# AMC_Box_Mainboard.net
KiCad netlist of a schematic drawn in Altium Designer
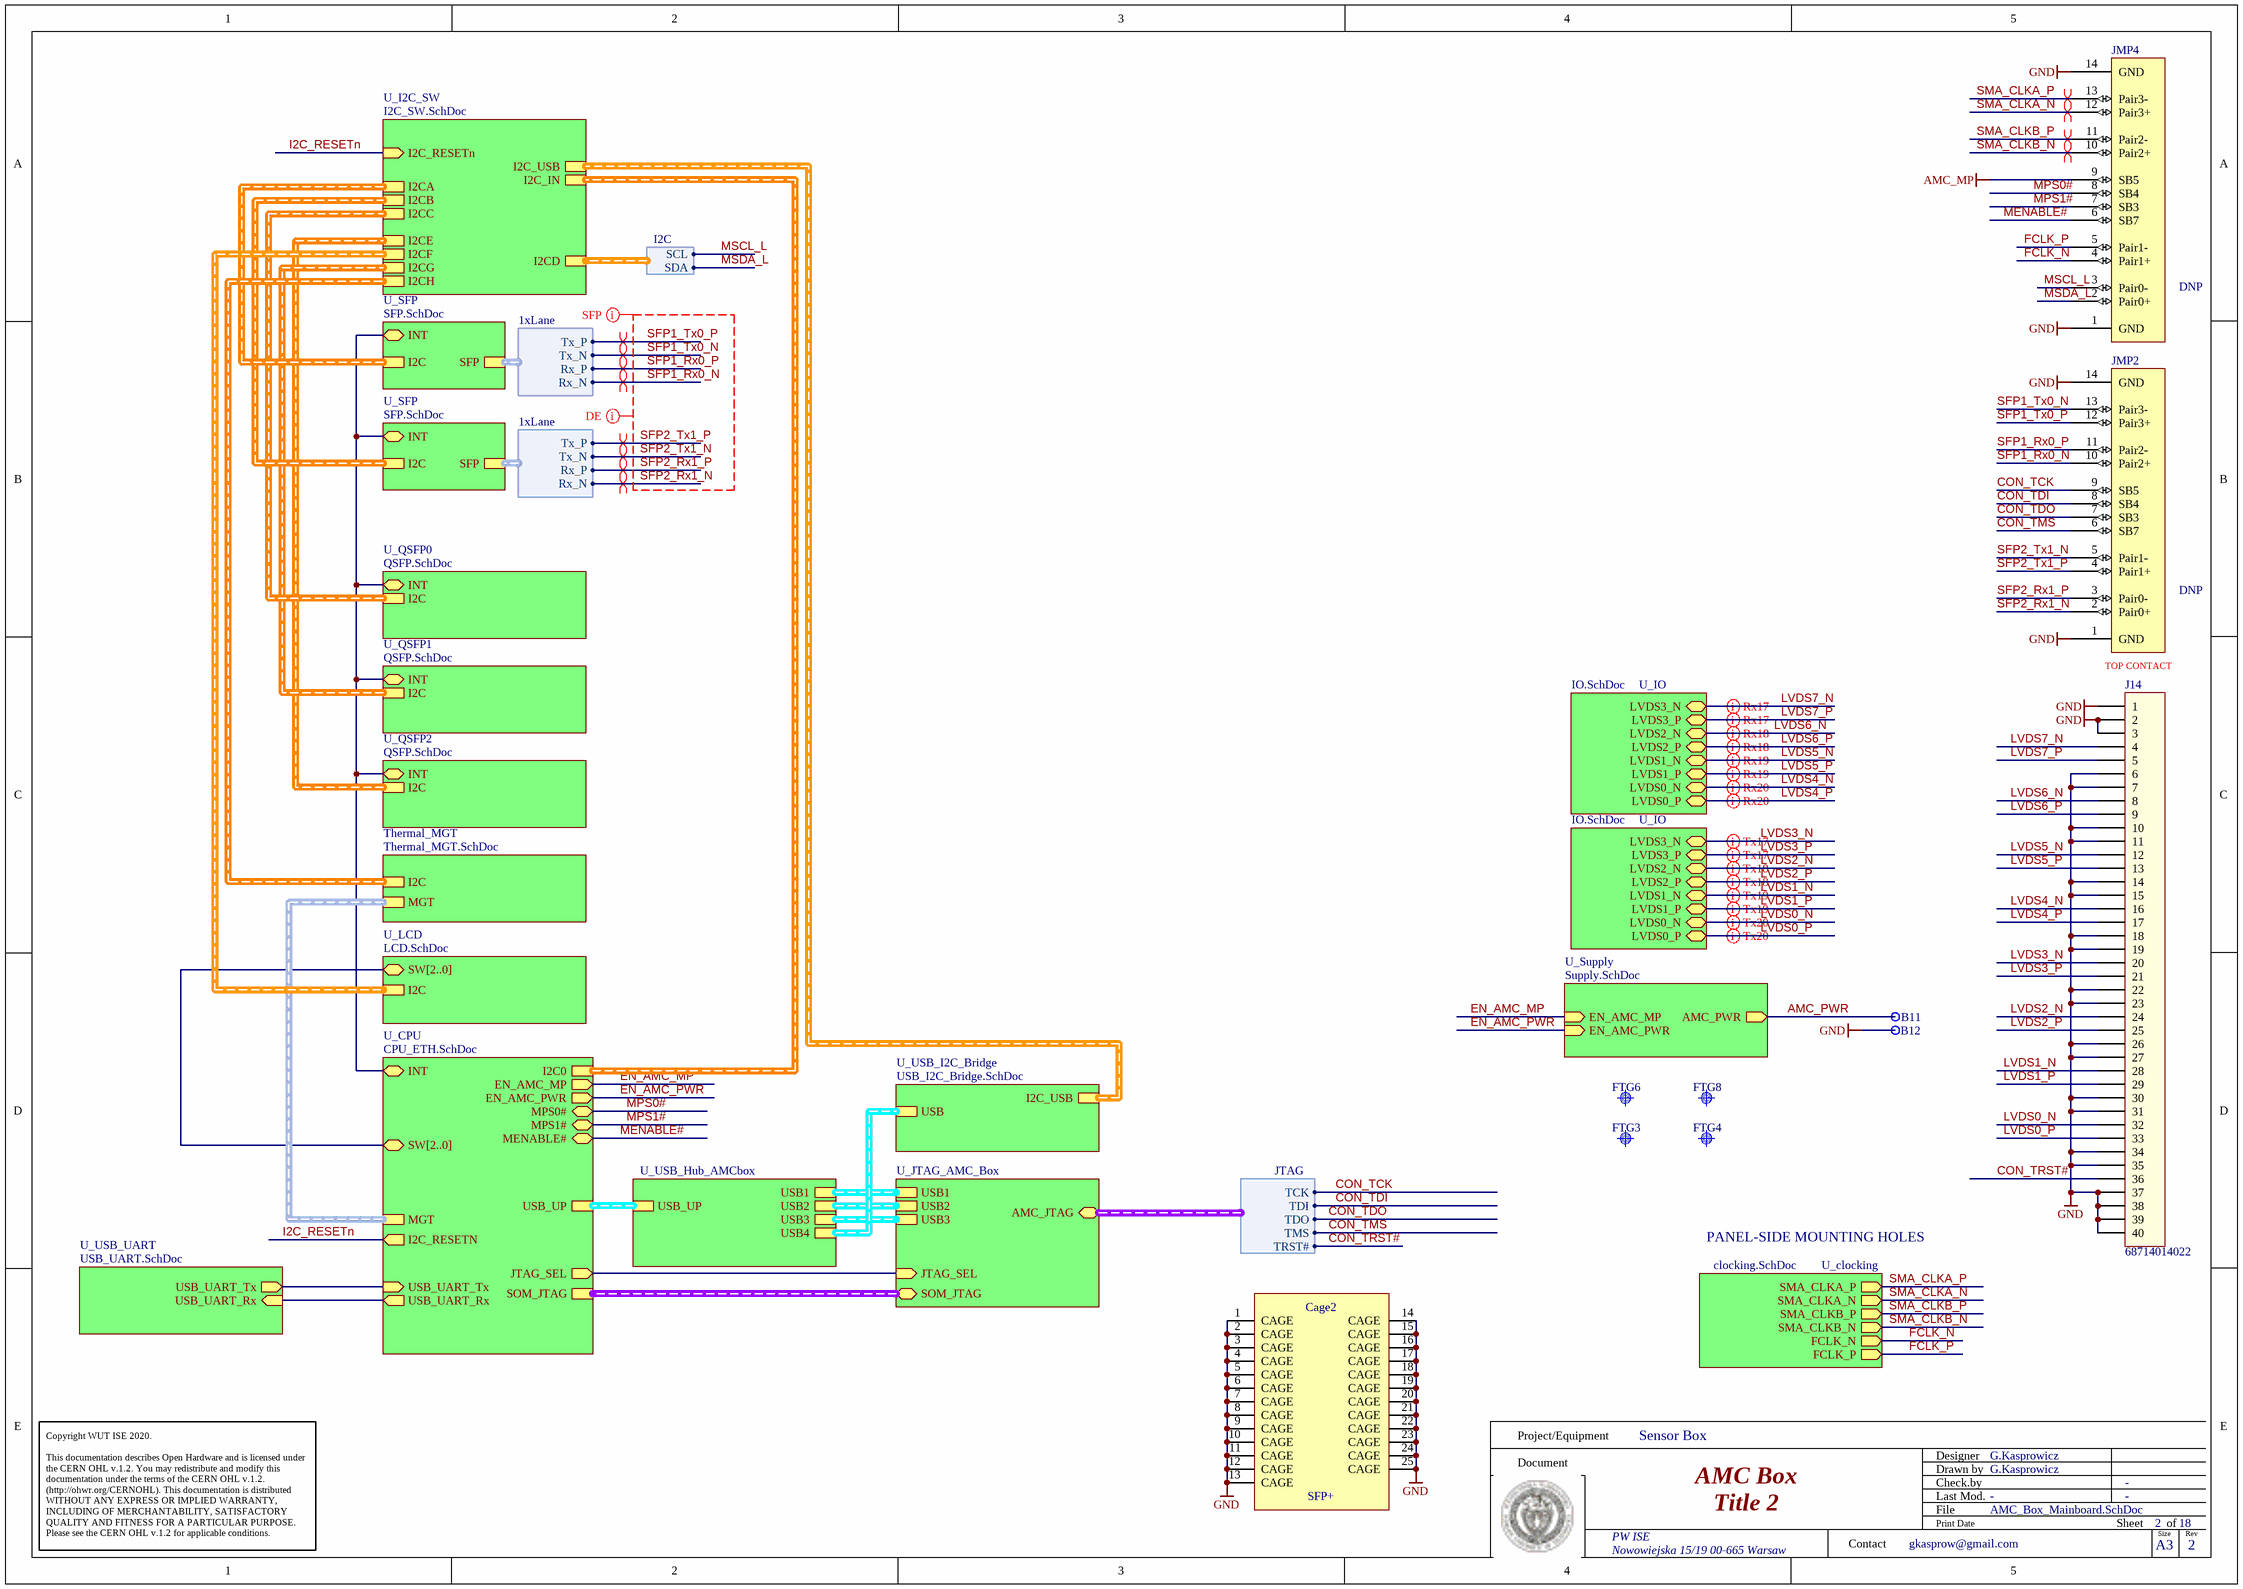
[diagram p0: AMC_Box_Mainboard.SchDoc]

(export (version "E")
  (design (tool "Eeschema 10.0.6"))
  (components
    (comp (ref "B11")
      (value "Plated Hole")
      (footprint "c200h150")
      (description "Single Terminal Socket")
      (fields (field (name "PART NUMBER") "PLATED_HOLE1.5_PAD2.0") (field (name "AUTHOR") "CERN DEM JLC"))
      (libsource (lib "Eletro-mechanical") (part "Single Terminal Socket"))
    )
    (comp (ref "B12")
      (value "Plated Hole")
      (footprint "c200h150")
      (description "Single Terminal Socket")
      (fields (field (name "PART NUMBER") "PLATED_HOLE1.5_PAD2.0") (field (name "AUTHOR") "CERN DEM JLC"))
      (libsource (lib "Eletro-mechanical") (part "Single Terminal Socket"))
    )
    (comp (ref "Cage2")
      (value "SFP+")
      (footprint "TYCO_2007263-1")
      (description "SFP 1x2 Cage (25Pins)")
      (fields
        (field (name "PART NUMBER") "TYCO_2007263-1")
        (field (name "MANUFACTURER") "TYCO ELECTRONICS")
        (field (name "AUTHOR") "CERN DEM JLC")
      )
      (libsource (lib "Connectors") (part "SFP 1x2 Cage (25Pins)"))
    )
    (comp (ref "FTG3")
      (value "Use only in PCB")
      (footprint "FIDUCIAL_TOP_S100-200")
      (description "Fiducial Target")
      (fields (field (name "PART NUMBER") "FIDUCIAL_TARGET_S100-200") (field (name "AUTHOR") "CERN DEM JLC"))
      (libsource (lib "Eletro-mechanical") (part "Fiducial Target"))
    )
    (comp (ref "FTG4")
      (value "Use only in PCB")
      (footprint "FIDUCIAL_TOP_C100-200")
      (description "Fiducial Target")
      (fields (field (name "PART NUMBER") "FIDUCIAL_TARGET_C100-200") (field (name "AUTHOR") "CERN DEM JLC"))
      (libsource (lib "Eletro-mechanical") (part "Fiducial Target"))
    )
    (comp (ref "FTG6")
      (value "Use only in PCB")
      (footprint "FIDUCIAL_TOP_S100-200")
      (description "Fiducial Target")
      (fields (field (name "PART NUMBER") "FIDUCIAL_TARGET_S100-200") (field (name "AUTHOR") "CERN DEM JLC"))
      (libsource (lib "Eletro-mechanical") (part "Fiducial Target"))
    )
    (comp (ref "FTG8")
      (value "Use only in PCB")
      (footprint "FIDUCIAL_TOP_C100-200")
      (description "Fiducial Target")
      (fields (field (name "PART NUMBER") "FIDUCIAL_TARGET_C100-200") (field (name "AUTHOR") "CERN DEM JLC"))
      (libsource (lib "Eletro-mechanical") (part "Fiducial Target"))
    )
    (comp (ref "J14")
      (value "68714014022")
      (footprint "68714014022")
      (description "0.50 mm SMT ZIF Horizontal Top Contact WR-FPC, 40 pins")
      (fields (field (name "PUBLISHER") "Wurth Elektronik"))
      (libsource (lib "Altium_FPC_CONNECTORS (rev17a)") (part "68714014022"))
    )
    (comp (ref "JMP2")
      (value "DNP")
      (footprint "3M_Twinax_SL8801/12-10DA5-00")
      (libsource (lib "LIBRARY_SCH") (part "DNP"))
    )
    (comp (ref "JMP4")
      (value "DNP")
      (footprint "3M_Twinax_SL8801/12-10DA5-00")
      (libsource (lib "LIBRARY_SCH") (part "DNP"))
    )
  )
  (nets
    (net (code "4") (name "/AMC_PWR") (class "Default")
      (node (ref "B11") (pin "1") (pinfunction "1_1") (pintype "bidirectional"))
    )
    (net (code "5") (name "/CON_TCK") (class "Default")
      (node (ref "JMP2") (pin "9") (pinfunction "SB5_9") (pintype "bidirectional"))
    )
    (net (code "6") (name "/CON_TDI") (class "Default")
      (node (ref "JMP2") (pin "8") (pinfunction "SB4_8") (pintype "bidirectional"))
    )
    (net (code "7") (name "/CON_TDO") (class "Default")
      (node (ref "JMP2") (pin "7") (pinfunction "SB3_7") (pintype "bidirectional"))
    )
    (net (code "8") (name "/CON_TMS") (class "Default")
      (node (ref "JMP2") (pin "6") (pinfunction "SB7_6") (pintype "bidirectional"))
    )
    (net (code "9") (name "/CON_TRST#") (class "Default")
      (node (ref "J14") (pin "36") (pinfunction "36_36") (pintype "passive"))
    )
    (net (code "12") (name "/FCLK_N") (class "Default")
      (node (ref "JMP4") (pin "4") (pinfunction "Pair1+_4") (pintype "bidirectional"))
    )
    (net (code "13") (name "/FCLK_P") (class "Default")
      (node (ref "JMP4") (pin "5") (pinfunction "Pair1-_5") (pintype "bidirectional"))
    )
    (net (code "26") (name "/LVDS0_N") (class "Default")
      (node (ref "J14") (pin "32") (pinfunction "32_32") (pintype "passive"))
    )
    (net (code "27") (name "/LVDS0_P") (class "Default")
      (node (ref "J14") (pin "33") (pinfunction "33_33") (pintype "passive"))
    )
    (net (code "28") (name "/LVDS1_N") (class "Default")
      (node (ref "J14") (pin "28") (pinfunction "28_28") (pintype "passive"))
    )
    (net (code "29") (name "/LVDS1_P") (class "Default")
      (node (ref "J14") (pin "29") (pinfunction "29_29") (pintype "passive"))
    )
    (net (code "30") (name "/LVDS2_N") (class "Default")
      (node (ref "J14") (pin "24") (pinfunction "24_24") (pintype "passive"))
    )
    (net (code "31") (name "/LVDS2_P") (class "Default")
      (node (ref "J14") (pin "25") (pinfunction "25_25") (pintype "passive"))
    )
    (net (code "32") (name "/LVDS3_N") (class "Default")
      (node (ref "J14") (pin "20") (pinfunction "20_20") (pintype "passive"))
    )
    (net (code "33") (name "/LVDS3_P") (class "Default")
      (node (ref "J14") (pin "21") (pinfunction "21_21") (pintype "passive"))
    )
    (net (code "34") (name "/LVDS4_N") (class "Default")
      (node (ref "J14") (pin "16") (pinfunction "16_16") (pintype "passive"))
    )
    (net (code "35") (name "/LVDS4_P") (class "Default")
      (node (ref "J14") (pin "17") (pinfunction "17_17") (pintype "passive"))
    )
    (net (code "36") (name "/LVDS5_N") (class "Default")
      (node (ref "J14") (pin "12") (pinfunction "12_12") (pintype "passive"))
    )
    (net (code "37") (name "/LVDS5_P") (class "Default")
      (node (ref "J14") (pin "13") (pinfunction "13_13") (pintype "passive"))
    )
    (net (code "38") (name "/LVDS6_N") (class "Default")
      (node (ref "J14") (pin "8") (pinfunction "8_8") (pintype "passive"))
    )
    (net (code "39") (name "/LVDS6_P") (class "Default")
      (node (ref "J14") (pin "9") (pinfunction "9_9") (pintype "passive"))
    )
    (net (code "40") (name "/LVDS7_N") (class "Default")
      (node (ref "J14") (pin "4") (pinfunction "4_4") (pintype "passive"))
    )
    (net (code "41") (name "/LVDS7_P") (class "Default")
      (node (ref "J14") (pin "5") (pinfunction "5_5") (pintype "passive"))
    )
    (net (code "42") (name "/MENABLE#") (class "Default")
      (node (ref "JMP4") (pin "6") (pinfunction "SB7_6") (pintype "bidirectional"))
    )
    (net (code "44") (name "/MPS0#") (class "Default")
      (node (ref "JMP4") (pin "8") (pinfunction "SB4_8") (pintype "bidirectional"))
    )
    (net (code "45") (name "/MPS1#") (class "Default")
      (node (ref "JMP4") (pin "7") (pinfunction "SB3_7") (pintype "bidirectional"))
    )
    (net (code "46") (name "/MSCL_L") (class "Default")
      (node (ref "JMP4") (pin "3") (pinfunction "Pair0-_3") (pintype "bidirectional"))
    )
    (net (code "47") (name "/MSDA_L") (class "Default")
      (node (ref "JMP4") (pin "2") (pinfunction "Pair0+_2") (pintype "bidirectional"))
    )
    (net (code "48") (name "/SFP1_Rx0_N") (class "Default")
      (node (ref "JMP2") (pin "10") (pinfunction "Pair2+_10") (pintype "bidirectional"))
    )
    (net (code "49") (name "/SFP1_Rx0_P") (class "Default")
      (node (ref "JMP2") (pin "11") (pinfunction "Pair2-_11") (pintype "bidirectional"))
    )
    (net (code "50") (name "/SFP1_Tx0_N") (class "Default")
      (node (ref "JMP2") (pin "13") (pinfunction "Pair3-_13") (pintype "bidirectional"))
    )
    (net (code "51") (name "/SFP1_Tx0_P") (class "Default")
      (node (ref "JMP2") (pin "12") (pinfunction "Pair3+_12") (pintype "bidirectional"))
    )
    (net (code "52") (name "/SFP2_Rx1_N") (class "Default")
      (node (ref "JMP2") (pin "2") (pinfunction "Pair0+_2") (pintype "bidirectional"))
    )
    (net (code "53") (name "/SFP2_Rx1_P") (class "Default")
      (node (ref "JMP2") (pin "3") (pinfunction "Pair0-_3") (pintype "bidirectional"))
    )
    (net (code "54") (name "/SFP2_Tx1_N") (class "Default")
      (node (ref "JMP2") (pin "5") (pinfunction "Pair1-_5") (pintype "bidirectional"))
    )
    (net (code "55") (name "/SFP2_Tx1_P") (class "Default")
      (node (ref "JMP2") (pin "4") (pinfunction "Pair1+_4") (pintype "bidirectional"))
    )
    (net (code "56") (name "/SMA_CLKA_N") (class "Default")
      (node (ref "JMP4") (pin "12") (pinfunction "Pair3+_12") (pintype "bidirectional"))
    )
    (net (code "57") (name "/SMA_CLKA_P") (class "Default")
      (node (ref "JMP4") (pin "13") (pinfunction "Pair3-_13") (pintype "bidirectional"))
    )
    (net (code "58") (name "/SMA_CLKB_N") (class "Default")
      (node (ref "JMP4") (pin "10") (pinfunction "Pair2+_10") (pintype "bidirectional"))
    )
    (net (code "59") (name "/SMA_CLKB_P") (class "Default")
      (node (ref "JMP4") (pin "11") (pinfunction "Pair2-_11") (pintype "bidirectional"))
    )
    (net (code "72") (name "AMC_MP") (class "Default")
      (node (ref "JMP4") (pin "9") (pinfunction "SB5_9") (pintype "bidirectional"))
    )
    (net (code "73") (name "GND") (class "Default")
      (node (ref "B12") (pin "1") (pinfunction "1_1") (pintype "bidirectional"))
      (node (ref "Cage2") (pin "1") (pinfunction "CAGE_1") (pintype "power_in"))
      (node (ref "Cage2") (pin "10") (pinfunction "CAGE_10") (pintype "power_in"))
      (node (ref "Cage2") (pin "11") (pinfunction "CAGE_11") (pintype "power_in"))
      (node (ref "Cage2") (pin "12") (pinfunction "CAGE_12") (pintype "power_in"))
      (node (ref "Cage2") (pin "13") (pinfunction "CAGE_13") (pintype "power_in"))
      (node (ref "Cage2") (pin "14") (pinfunction "CAGE_14") (pintype "power_in"))
      (node (ref "Cage2") (pin "15") (pinfunction "CAGE_15") (pintype "power_in"))
      (node (ref "Cage2") (pin "16") (pinfunction "CAGE_16") (pintype "power_in"))
      (node (ref "Cage2") (pin "17") (pinfunction "CAGE_17") (pintype "power_in"))
      (node (ref "Cage2") (pin "18") (pinfunction "CAGE_18") (pintype "power_in"))
      (node (ref "Cage2") (pin "19") (pinfunction "CAGE_19") (pintype "power_in"))
      (node (ref "Cage2") (pin "2") (pinfunction "CAGE_2") (pintype "power_in"))
      (node (ref "Cage2") (pin "20") (pinfunction "CAGE_20") (pintype "power_in"))
      (node (ref "Cage2") (pin "21") (pinfunction "CAGE_21") (pintype "power_in"))
      (node (ref "Cage2") (pin "22") (pinfunction "CAGE_22") (pintype "power_in"))
      (node (ref "Cage2") (pin "23") (pinfunction "CAGE_23") (pintype "power_in"))
      (node (ref "Cage2") (pin "24") (pinfunction "CAGE_24") (pintype "power_in"))
      (node (ref "Cage2") (pin "25") (pinfunction "CAGE_25") (pintype "power_in"))
      (node (ref "Cage2") (pin "3") (pinfunction "CAGE_3") (pintype "power_in"))
      (node (ref "Cage2") (pin "4") (pinfunction "CAGE_4") (pintype "power_in"))
      (node (ref "Cage2") (pin "5") (pinfunction "CAGE_5") (pintype "power_in"))
      (node (ref "Cage2") (pin "6") (pinfunction "CAGE_6") (pintype "power_in"))
      (node (ref "Cage2") (pin "7") (pinfunction "CAGE_7") (pintype "power_in"))
      (node (ref "Cage2") (pin "8") (pinfunction "CAGE_8") (pintype "power_in"))
      (node (ref "Cage2") (pin "9") (pinfunction "CAGE_9") (pintype "power_in"))
      (node (ref "J14") (pin "1") (pinfunction "1_1") (pintype "passive"))
      (node (ref "J14") (pin "10") (pinfunction "10_10") (pintype "passive"))
      (node (ref "J14") (pin "11") (pinfunction "11_11") (pintype "passive"))
      (node (ref "J14") (pin "14") (pinfunction "14_14") (pintype "passive"))
      (node (ref "J14") (pin "15") (pinfunction "15_15") (pintype "passive"))
      (node (ref "J14") (pin "18") (pinfunction "18_18") (pintype "passive"))
      (node (ref "J14") (pin "19") (pinfunction "19_19") (pintype "passive"))
      (node (ref "J14") (pin "2") (pinfunction "2_2") (pintype "passive"))
      (node (ref "J14") (pin "22") (pinfunction "22_22") (pintype "passive"))
      (node (ref "J14") (pin "23") (pinfunction "23_23") (pintype "passive"))
      (node (ref "J14") (pin "26") (pinfunction "26_26") (pintype "passive"))
      (node (ref "J14") (pin "27") (pinfunction "27_27") (pintype "passive"))
      (node (ref "J14") (pin "3") (pinfunction "3_3") (pintype "passive"))
      (node (ref "J14") (pin "30") (pinfunction "30_30") (pintype "passive"))
      (node (ref "J14") (pin "31") (pinfunction "31_31") (pintype "passive"))
      (node (ref "J14") (pin "34") (pinfunction "34_34") (pintype "passive"))
      (node (ref "J14") (pin "35") (pinfunction "35_35") (pintype "passive"))
      (node (ref "J14") (pin "37") (pinfunction "37_37") (pintype "passive"))
      (node (ref "J14") (pin "38") (pinfunction "38_38") (pintype "passive"))
      (node (ref "J14") (pin "39") (pinfunction "39_39") (pintype "passive"))
      (node (ref "J14") (pin "40") (pinfunction "40_40") (pintype "passive"))
      (node (ref "J14") (pin "6") (pinfunction "6_6") (pintype "passive"))
      (node (ref "J14") (pin "7") (pinfunction "7_7") (pintype "passive"))
      (node (ref "JMP2") (pin "1") (pinfunction "GND_1") (pintype "power_in"))
      (node (ref "JMP2") (pin "14") (pinfunction "GND_14") (pintype "power_in"))
      (node (ref "JMP4") (pin "1") (pinfunction "GND_1") (pintype "power_in"))
      (node (ref "JMP4") (pin "14") (pinfunction "GND_14") (pintype "power_in"))
    )
  )
)
